# kilo.net
KiCad netlist of a schematic drawn in EAGLE
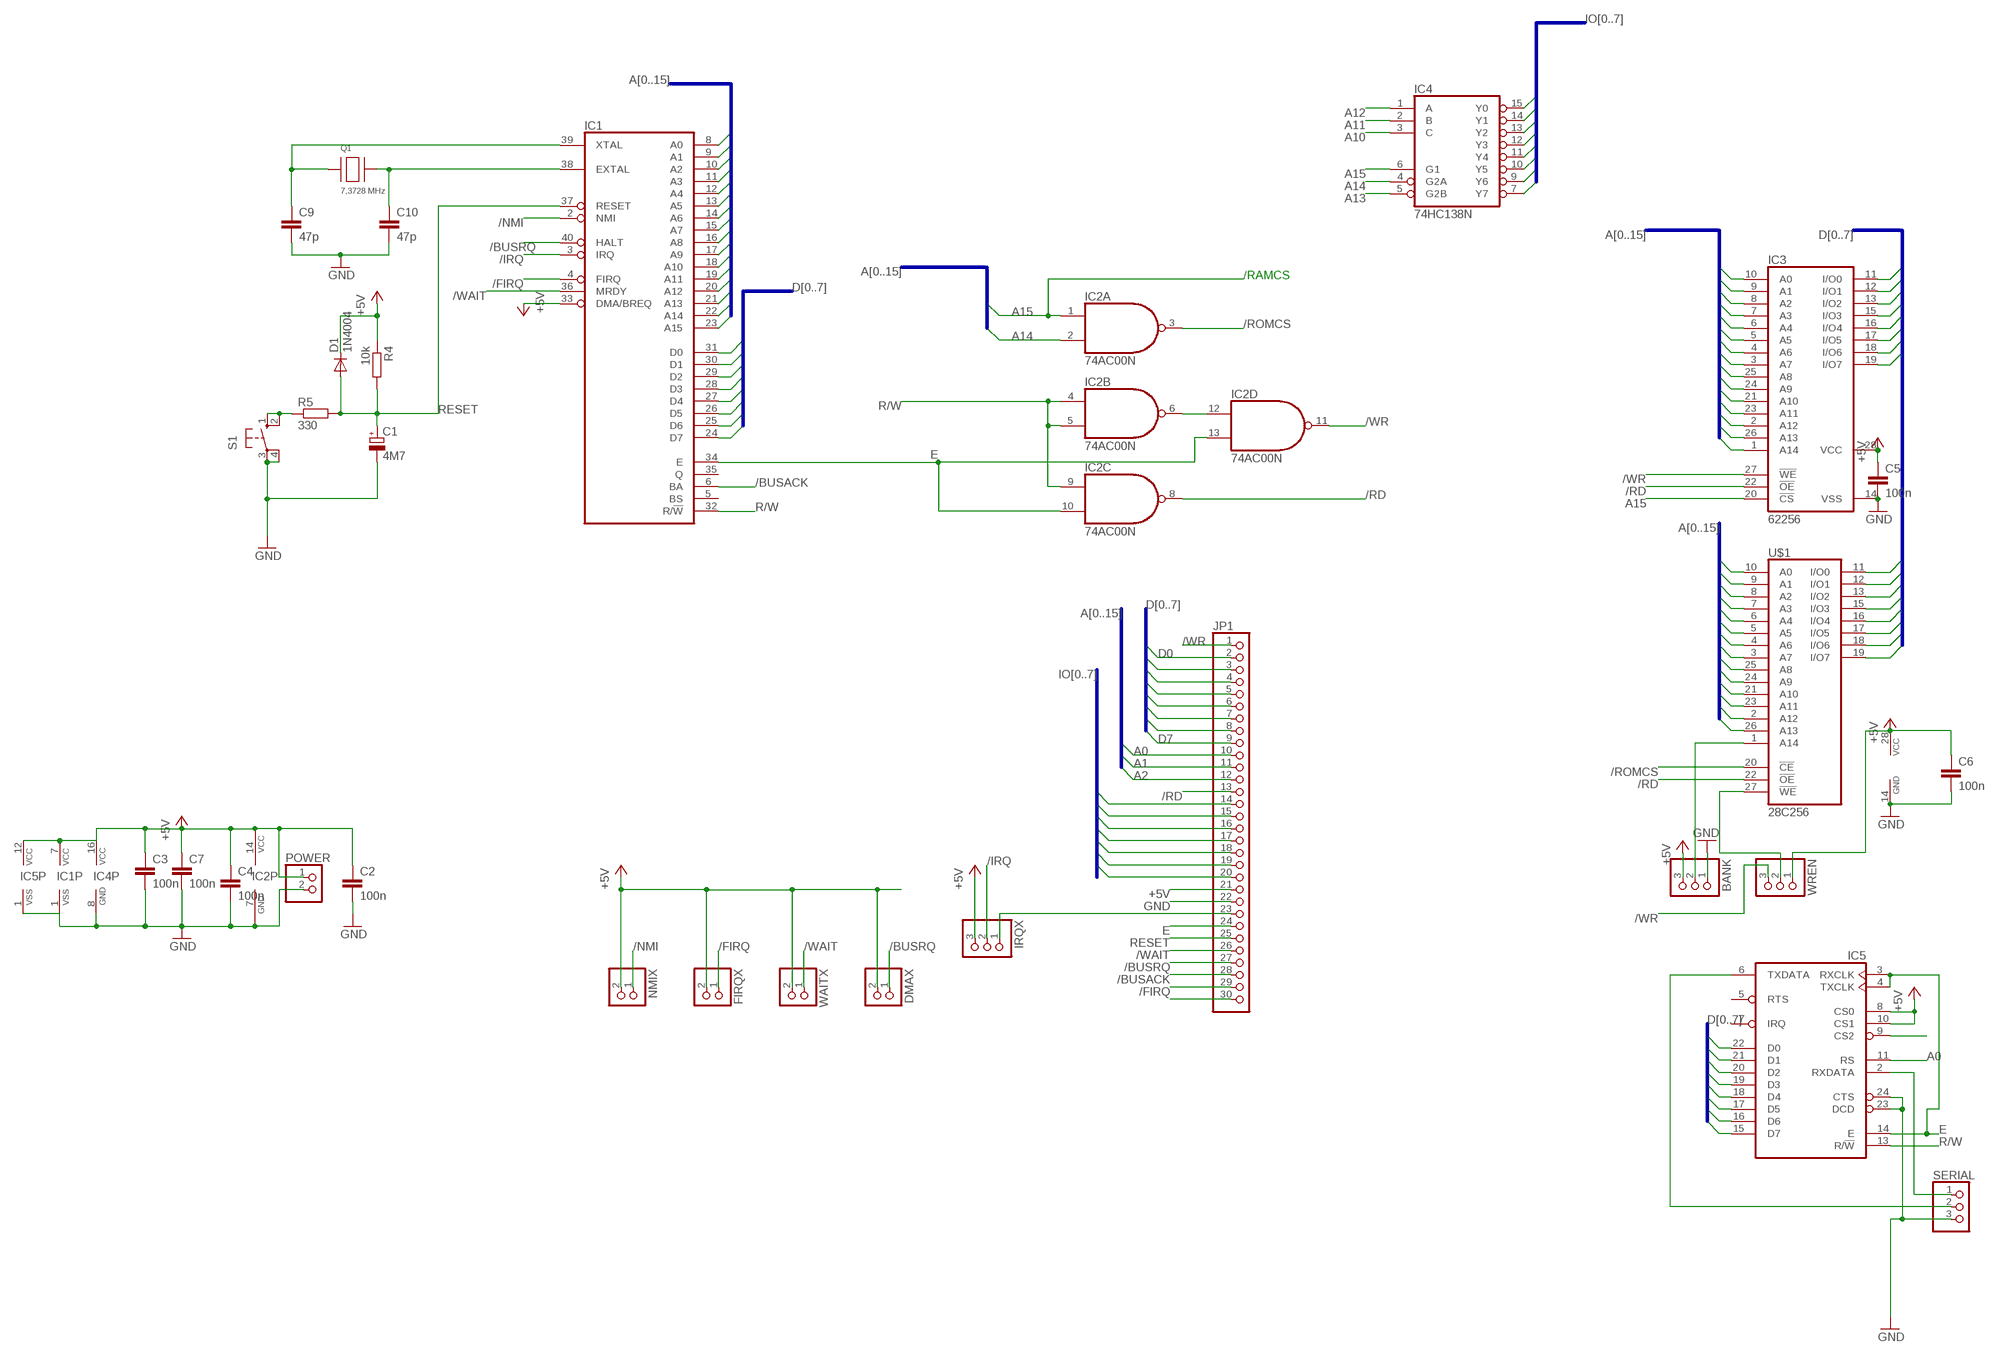
[diagram p0: schematic, sheet 1]

(export (version "E")
  (design (tool "Eeschema 10.0.6"))
  (components
    (comp (ref "BANK")
      (value "PINHD-1X3")
      (footprint "eagle-import:1X03")
      (libsource (lib "eagle-import") (part "PINHD-1X3"))
    )
    (comp (ref "C1")
      (value "4M7")
      (footprint "eagle-import:E2,5-6")
      (libsource (lib "eagle-import") (part "CPOL-EUE2.5-6"))
    )
    (comp (ref "C2")
      (value "100n")
      (footprint "eagle-import:C025-030X050")
      (libsource (lib "eagle-import") (part "C-EU025-030X050"))
    )
    (comp (ref "C3")
      (value "100n")
      (footprint "eagle-import:C025-030X050")
      (libsource (lib "eagle-import") (part "C-EU025-030X050"))
    )
    (comp (ref "C4")
      (value "100n")
      (footprint "eagle-import:C025-030X050")
      (libsource (lib "eagle-import") (part "C-EU025-030X050"))
    )
    (comp (ref "C5")
      (value "100n")
      (footprint "eagle-import:C025-030X050")
      (libsource (lib "eagle-import") (part "C-EU025-030X050"))
    )
    (comp (ref "C6")
      (value "100n")
      (footprint "eagle-import:C025-030X050")
      (libsource (lib "eagle-import") (part "C-EU025-030X050"))
    )
    (comp (ref "C7")
      (value "100n")
      (footprint "eagle-import:C025-030X050")
      (libsource (lib "eagle-import") (part "C-EU025-030X050"))
    )
    (comp (ref "C9")
      (value "47p")
      (footprint "eagle-import:C025-030X050")
      (libsource (lib "eagle-import") (part "C-EU025-030X050"))
    )
    (comp (ref "C10")
      (value "47p")
      (footprint "eagle-import:C025-030X050")
      (libsource (lib "eagle-import") (part "C-EU025-030X050"))
    )
    (comp (ref "D1")
      (value "1N4004")
      (footprint "eagle-import:DO41-10")
      (libsource (lib "eagle-import") (part "1N4004"))
    )
    (comp (ref "DMAX")
      (value "PINHD-1X2")
      (footprint "eagle-import:1X02")
      (libsource (lib "eagle-import") (part "PINHD-1X2"))
    )
    (comp (ref "FIRQX")
      (value "PINHD-1X2")
      (footprint "eagle-import:1X02")
      (libsource (lib "eagle-import") (part "PINHD-1X2"))
    )
    (comp (ref "IC1")
      (value "6809")
      (footprint "eagle-import:DIL40")
      (fields (field (name "MF") "NTE ELECTRONICS") (field (name "MPN") "NTE6809"))
      (libsource (lib "eagle-import") (part "6809"))
    )
    (comp (ref "IC2")
      (value "74AC00N")
      (footprint "eagle-import:DIL14")
      (libsource (lib "eagle-import") (part "7400NALS"))
    )
    (comp (ref "IC3")
      (value "62256")
      (footprint "eagle-import:DIL28-6")
      (libsource (lib "eagle-import") (part "62256P"))
    )
    (comp (ref "IC4")
      (value "74HC138N")
      (footprint "eagle-import:DIL16")
      (libsource (lib "eagle-import") (part "74138NHC"))
    )
    (comp (ref "IC5")
      (value "6850")
      (footprint "eagle-import:DIL24")
      (fields (field (name "MF") "NTE ELECTRONICS") (field (name "MPN") "NTE6850"))
      (libsource (lib "eagle-import") (part "6850"))
    )
    (comp (ref "IRQX")
      (value "PINHD-1X3")
      (footprint "eagle-import:1X03")
      (libsource (lib "eagle-import") (part "PINHD-1X3"))
    )
    (comp (ref "JP1")
      (value "PINHD-1X30")
      (footprint "eagle-import:1X30")
      (libsource (lib "eagle-import") (part "PINHD-1X30"))
    )
    (comp (ref "NMIX")
      (value "PINHD-1X2")
      (footprint "eagle-import:1X02")
      (libsource (lib "eagle-import") (part "PINHD-1X2"))
    )
    (comp (ref "POWER")
      (value "PINHD-1X2")
      (footprint "eagle-import:1X02")
      (libsource (lib "eagle-import") (part "PINHD-1X2"))
    )
    (comp (ref "Q1")
      (value "7,3728 MHz")
      (footprint "eagle-import:HC49US")
      (libsource (lib "eagle-import") (part "306010080_XTAL_8MHZ_HC49US"))
    )
    (comp (ref "R4")
      (value "10k")
      (footprint "eagle-import:0207_7")
      (libsource (lib "eagle-import") (part "R-EU_0207/7"))
    )
    (comp (ref "R5")
      (value "330")
      (footprint "eagle-import:0207_7")
      (libsource (lib "eagle-import") (part "R-EU_0207/7"))
    )
    (comp (ref "S1")
      (value "40-XX")
      (footprint "eagle-import:B3F-40XX")
      (fields (field (name "MF") "OMRON COMPONENTS USA") (field (name "MPN") "B3F-4000"))
      (libsource (lib "eagle-import") (part "40-XX"))
    )
    (comp (ref "SERIAL")
      (value "PINHD-1X3")
      (footprint "eagle-import:1X03")
      (libsource (lib "eagle-import") (part "PINHD-1X3"))
    )
    (comp (ref "U$1")
      (value "28C256")
      (footprint "eagle-import:DIL28")
      (libsource (lib "eagle-import") (part "28C256"))
    )
    (comp (ref "WAITX")
      (value "PINHD-1X2")
      (footprint "eagle-import:1X02")
      (libsource (lib "eagle-import") (part "PINHD-1X2"))
    )
    (comp (ref "WREN")
      (value "PINHD-1X3")
      (footprint "eagle-import:1X03")
      (libsource (lib "eagle-import") (part "PINHD-1X3"))
    )
  )
  (nets
    (net (code "1") (name "+5V") (class "Default")
      (node (ref "BANK") (pin "3") (pinfunction "3_3") (pintype "passive"))
      (node (ref "C2") (pin "1") (pinfunction "1_1") (pintype "passive"))
      (node (ref "C3") (pin "1") (pinfunction "1_1") (pintype "passive"))
      (node (ref "C4") (pin "1") (pinfunction "1_1") (pintype "passive"))
      (node (ref "C5") (pin "1") (pinfunction "1_1") (pintype "passive"))
      (node (ref "C6") (pin "1") (pinfunction "1_1") (pintype "passive"))
      (node (ref "C7") (pin "1") (pinfunction "1_1") (pintype "passive"))
      (node (ref "D1") (pin "C") (pinfunction "C_C") (pintype "passive"))
      (node (ref "DMAX") (pin "2") (pinfunction "2_2") (pintype "passive"))
      (node (ref "FIRQX") (pin "2") (pinfunction "2_2") (pintype "passive"))
      (node (ref "IC1") (pin "33") (pinfunction "DMA/BREQ_33") (pintype "input"))
      (node (ref "IC1") (pin "7") (pinfunction "VCC_7") (pintype "power_in"))
      (node (ref "IC2") (pin "14") (pinfunction "VCC_14") (pintype "power_in"))
      (node (ref "IC3") (pin "28") (pinfunction "VCC_28") (pintype "power_in"))
      (node (ref "IC4") (pin "16") (pinfunction "VCC_16") (pintype "power_in"))
      (node (ref "IC5") (pin "10") (pinfunction "CS1_10") (pintype "input"))
      (node (ref "IC5") (pin "12") (pinfunction "VCC_12") (pintype "power_in"))
      (node (ref "IC5") (pin "8") (pinfunction "CS0_8") (pintype "input"))
      (node (ref "IRQX") (pin "3") (pinfunction "3_3") (pintype "passive"))
      (node (ref "JP1") (pin "21") (pinfunction "21_21") (pintype "passive"))
      (node (ref "NMIX") (pin "2") (pinfunction "2_2") (pintype "passive"))
      (node (ref "POWER") (pin "1") (pinfunction "1_1") (pintype "passive"))
      (node (ref "R4") (pin "1") (pinfunction "1_1") (pintype "passive"))
      (node (ref "U$1") (pin "28") (pinfunction "VCC_28") (pintype "power_in"))
      (node (ref "WAITX") (pin "2") (pinfunction "2_2") (pintype "passive"))
      (node (ref "WREN") (pin "1") (pinfunction "1_1") (pintype "passive"))
    )
    (net (code "5") (name "A0") (class "Default")
      (node (ref "IC1") (pin "8") (pinfunction "A0_8") (pintype "tri_state"))
      (node (ref "IC3") (pin "10") (pinfunction "A0_10") (pintype "input"))
      (node (ref "IC5") (pin "11") (pinfunction "RS_11") (pintype "input"))
      (node (ref "JP1") (pin "10") (pinfunction "10_10") (pintype "passive"))
      (node (ref "U$1") (pin "10") (pinfunction "A0_10") (pintype "input"))
    )
    (net (code "6") (name "A1") (class "Default")
      (node (ref "IC1") (pin "9") (pinfunction "A1_9") (pintype "tri_state"))
      (node (ref "IC3") (pin "9") (pinfunction "A1_9") (pintype "input"))
      (node (ref "JP1") (pin "11") (pinfunction "11_11") (pintype "passive"))
      (node (ref "U$1") (pin "9") (pinfunction "A1_9") (pintype "input"))
    )
    (net (code "7") (name "A2") (class "Default")
      (node (ref "IC1") (pin "10") (pinfunction "A2_10") (pintype "tri_state"))
      (node (ref "IC3") (pin "8") (pinfunction "A2_8") (pintype "input"))
      (node (ref "JP1") (pin "12") (pinfunction "12_12") (pintype "passive"))
      (node (ref "U$1") (pin "8") (pinfunction "A2_8") (pintype "input"))
    )
    (net (code "8") (name "A3") (class "Default")
      (node (ref "IC1") (pin "11") (pinfunction "A3_11") (pintype "tri_state"))
      (node (ref "IC3") (pin "7") (pinfunction "A3_7") (pintype "input"))
      (node (ref "U$1") (pin "7") (pinfunction "A3_7") (pintype "input"))
    )
    (net (code "9") (name "A4") (class "Default")
      (node (ref "IC1") (pin "12") (pinfunction "A4_12") (pintype "tri_state"))
      (node (ref "IC3") (pin "6") (pinfunction "A4_6") (pintype "input"))
      (node (ref "U$1") (pin "6") (pinfunction "A4_6") (pintype "input"))
    )
    (net (code "10") (name "A5") (class "Default")
      (node (ref "IC1") (pin "13") (pinfunction "A5_13") (pintype "tri_state"))
      (node (ref "IC3") (pin "5") (pinfunction "A5_5") (pintype "input"))
      (node (ref "U$1") (pin "5") (pinfunction "A5_5") (pintype "input"))
    )
    (net (code "11") (name "A6") (class "Default")
      (node (ref "IC1") (pin "14") (pinfunction "A6_14") (pintype "tri_state"))
      (node (ref "IC3") (pin "4") (pinfunction "A6_4") (pintype "input"))
      (node (ref "U$1") (pin "4") (pinfunction "A6_4") (pintype "input"))
    )
    (net (code "12") (name "A7") (class "Default")
      (node (ref "IC1") (pin "15") (pinfunction "A7_15") (pintype "tri_state"))
      (node (ref "IC3") (pin "3") (pinfunction "A7_3") (pintype "input"))
      (node (ref "U$1") (pin "3") (pinfunction "A7_3") (pintype "input"))
    )
    (net (code "13") (name "A8") (class "Default")
      (node (ref "IC1") (pin "16") (pinfunction "A8_16") (pintype "tri_state"))
      (node (ref "IC3") (pin "25") (pinfunction "A8_25") (pintype "input"))
      (node (ref "U$1") (pin "25") (pinfunction "A8_25") (pintype "input"))
    )
    (net (code "14") (name "A9") (class "Default")
      (node (ref "IC1") (pin "17") (pinfunction "A9_17") (pintype "tri_state"))
      (node (ref "IC3") (pin "24") (pinfunction "A9_24") (pintype "input"))
      (node (ref "U$1") (pin "24") (pinfunction "A9_24") (pintype "input"))
    )
    (net (code "15") (name "A10") (class "Default")
      (node (ref "IC1") (pin "18") (pinfunction "A10_18") (pintype "tri_state"))
      (node (ref "IC3") (pin "21") (pinfunction "A10_21") (pintype "input"))
      (node (ref "IC4") (pin "3") (pinfunction "C_3") (pintype "input"))
      (node (ref "U$1") (pin "21") (pinfunction "A10_21") (pintype "input"))
    )
    (net (code "16") (name "A11") (class "Default")
      (node (ref "IC1") (pin "19") (pinfunction "A11_19") (pintype "tri_state"))
      (node (ref "IC3") (pin "23") (pinfunction "A11_23") (pintype "input"))
      (node (ref "IC4") (pin "2") (pinfunction "B_2") (pintype "input"))
      (node (ref "U$1") (pin "23") (pinfunction "A11_23") (pintype "input"))
    )
    (net (code "17") (name "A12") (class "Default")
      (node (ref "IC1") (pin "20") (pinfunction "A12_20") (pintype "tri_state"))
      (node (ref "IC3") (pin "2") (pinfunction "A12_2") (pintype "input"))
      (node (ref "IC4") (pin "1") (pinfunction "A_1") (pintype "input"))
      (node (ref "U$1") (pin "2") (pinfunction "A12_2") (pintype "input"))
    )
    (net (code "18") (name "A13") (class "Default")
      (node (ref "IC1") (pin "21") (pinfunction "A13_21") (pintype "tri_state"))
      (node (ref "IC3") (pin "26") (pinfunction "A13_26") (pintype "input"))
      (node (ref "IC4") (pin "5") (pinfunction "G2B_5") (pintype "input"))
      (node (ref "U$1") (pin "26") (pinfunction "A13_26") (pintype "input"))
    )
    (net (code "19") (name "A14") (class "Default")
      (node (ref "IC1") (pin "22") (pinfunction "A14_22") (pintype "tri_state"))
      (node (ref "IC2") (pin "2") (pinfunction "I1_2") (pintype "input"))
      (node (ref "IC3") (pin "1") (pinfunction "A14_1") (pintype "input"))
      (node (ref "IC4") (pin "4") (pinfunction "G2A_4") (pintype "input"))
    )
    (net (code "20") (name "A15") (class "Default")
      (node (ref "IC1") (pin "23") (pinfunction "A15_23") (pintype "tri_state"))
      (node (ref "IC2") (pin "1") (pinfunction "I0_1") (pintype "input"))
      (node (ref "IC3") (pin "20") (pinfunction "~{CS}_20") (pintype "input"))
      (node (ref "IC4") (pin "6") (pinfunction "G1_6") (pintype "input"))
    )
    (net (code "21") (name "D0") (class "Default")
      (node (ref "IC1") (pin "31") (pinfunction "D0_31") (pintype "bidirectional"))
      (node (ref "IC3") (pin "11") (pinfunction "I/O0_11") (pintype "bidirectional"))
      (node (ref "IC5") (pin "22") (pinfunction "D0_22") (pintype "bidirectional"))
      (node (ref "JP1") (pin "2") (pinfunction "2_2") (pintype "passive"))
      (node (ref "U$1") (pin "11") (pinfunction "I/O0_11") (pintype "tri_state"))
    )
    (net (code "22") (name "D1") (class "Default")
      (node (ref "IC1") (pin "30") (pinfunction "D1_30") (pintype "bidirectional"))
      (node (ref "IC3") (pin "12") (pinfunction "I/O1_12") (pintype "bidirectional"))
      (node (ref "IC5") (pin "21") (pinfunction "D1_21") (pintype "bidirectional"))
      (node (ref "JP1") (pin "3") (pinfunction "3_3") (pintype "passive"))
      (node (ref "U$1") (pin "12") (pinfunction "I/O1_12") (pintype "tri_state"))
    )
    (net (code "23") (name "D2") (class "Default")
      (node (ref "IC1") (pin "29") (pinfunction "D2_29") (pintype "bidirectional"))
      (node (ref "IC3") (pin "13") (pinfunction "I/O2_13") (pintype "bidirectional"))
      (node (ref "IC5") (pin "20") (pinfunction "D2_20") (pintype "bidirectional"))
      (node (ref "JP1") (pin "4") (pinfunction "4_4") (pintype "passive"))
      (node (ref "U$1") (pin "13") (pinfunction "I/O2_13") (pintype "tri_state"))
    )
    (net (code "24") (name "D3") (class "Default")
      (node (ref "IC1") (pin "28") (pinfunction "D3_28") (pintype "bidirectional"))
      (node (ref "IC3") (pin "15") (pinfunction "I/O3_15") (pintype "bidirectional"))
      (node (ref "IC5") (pin "19") (pinfunction "D3_19") (pintype "bidirectional"))
      (node (ref "JP1") (pin "5") (pinfunction "5_5") (pintype "passive"))
      (node (ref "U$1") (pin "15") (pinfunction "I/O3_15") (pintype "tri_state"))
    )
    (net (code "25") (name "D4") (class "Default")
      (node (ref "IC1") (pin "27") (pinfunction "D4_27") (pintype "bidirectional"))
      (node (ref "IC3") (pin "16") (pinfunction "I/O4_16") (pintype "bidirectional"))
      (node (ref "IC5") (pin "18") (pinfunction "D4_18") (pintype "bidirectional"))
      (node (ref "JP1") (pin "6") (pinfunction "6_6") (pintype "passive"))
      (node (ref "U$1") (pin "16") (pinfunction "I/O4_16") (pintype "tri_state"))
    )
    (net (code "26") (name "D5") (class "Default")
      (node (ref "IC1") (pin "26") (pinfunction "D5_26") (pintype "bidirectional"))
      (node (ref "IC3") (pin "17") (pinfunction "I/O5_17") (pintype "bidirectional"))
      (node (ref "IC5") (pin "17") (pinfunction "D5_17") (pintype "bidirectional"))
      (node (ref "JP1") (pin "7") (pinfunction "7_7") (pintype "passive"))
      (node (ref "U$1") (pin "17") (pinfunction "I/O5_17") (pintype "tri_state"))
    )
    (net (code "27") (name "D6") (class "Default")
      (node (ref "IC1") (pin "25") (pinfunction "D6_25") (pintype "bidirectional"))
      (node (ref "IC3") (pin "18") (pinfunction "I/O6_18") (pintype "bidirectional"))
      (node (ref "IC5") (pin "16") (pinfunction "D6_16") (pintype "bidirectional"))
      (node (ref "JP1") (pin "8") (pinfunction "8_8") (pintype "passive"))
      (node (ref "U$1") (pin "18") (pinfunction "I/O6_18") (pintype "tri_state"))
    )
    (net (code "28") (name "D7") (class "Default")
      (node (ref "IC1") (pin "24") (pinfunction "D7_24") (pintype "bidirectional"))
      (node (ref "IC3") (pin "19") (pinfunction "I/O7_19") (pintype "bidirectional"))
      (node (ref "IC5") (pin "15") (pinfunction "D7_15") (pintype "bidirectional"))
      (node (ref "JP1") (pin "9") (pinfunction "9_9") (pintype "passive"))
      (node (ref "U$1") (pin "19") (pinfunction "I/O7_19") (pintype "tri_state"))
    )
    (net (code "29") (name "E") (class "Default")
      (node (ref "IC1") (pin "34") (pinfunction "E_34") (pintype "output"))
      (node (ref "IC2") (pin "10") (pinfunction "I1_10") (pintype "input"))
      (node (ref "IC2") (pin "13") (pinfunction "I1_13") (pintype "input"))
      (node (ref "IC5") (pin "14") (pinfunction "E_14") (pintype "input"))
      (node (ref "IC5") (pin "3") (pinfunction "RXCLK_3") (pintype "input"))
      (node (ref "IC5") (pin "4") (pinfunction "TXCLK_4") (pintype "input"))
      (node (ref "JP1") (pin "24") (pinfunction "24_24") (pintype "passive"))
    )
    (net (code "30") (name "GND") (class "Default")
      (node (ref "BANK") (pin "1") (pinfunction "1_1") (pintype "passive"))
      (node (ref "C1") (pin "-") (pinfunction "-_-") (pintype "passive"))
      (node (ref "C10") (pin "2") (pinfunction "2_2") (pintype "passive"))
      (node (ref "C2") (pin "2") (pinfunction "2_2") (pintype "passive"))
      (node (ref "C3") (pin "2") (pinfunction "2_2") (pintype "passive"))
      (node (ref "C4") (pin "2") (pinfunction "2_2") (pintype "passive"))
      (node (ref "C5") (pin "2") (pinfunction "2_2") (pintype "passive"))
      (node (ref "C6") (pin "2") (pinfunction "2_2") (pintype "passive"))
      (node (ref "C7") (pin "2") (pinfunction "2_2") (pintype "passive"))
      (node (ref "C9") (pin "2") (pinfunction "2_2") (pintype "passive"))
      (node (ref "IC1") (pin "1") (pinfunction "VSS_1") (pintype "power_in"))
      (node (ref "IC2") (pin "7") (pinfunction "GND_7") (pintype "power_in"))
      (node (ref "IC3") (pin "14") (pinfunction "VSS_14") (pintype "power_in"))
      (node (ref "IC4") (pin "8") (pinfunction "GND_8") (pintype "power_in"))
      (node (ref "IC5") (pin "1") (pinfunction "VSS_1") (pintype "power_in"))
      (node (ref "IC5") (pin "23") (pinfunction "DCD_23") (pintype "input"))
      (node (ref "IC5") (pin "24") (pinfunction "CTS_24") (pintype "input"))
      (node (ref "JP1") (pin "22") (pinfunction "22_22") (pintype "passive"))
      (node (ref "POWER") (pin "2") (pinfunction "2_2") (pintype "passive"))
      (node (ref "S1") (pin "3") (pinfunction "P_3") (pintype "passive"))
      (node (ref "S1") (pin "4") (pinfunction "P1_4") (pintype "passive"))
      (node (ref "SERIAL") (pin "3") (pinfunction "3_3") (pintype "passive"))
      (node (ref "U$1") (pin "14") (pinfunction "GND_14") (pintype "power_in"))
    )
    (net (code "31") (name "IO0") (class "Default")
      (node (ref "IC4") (pin "15") (pinfunction "Y0_15") (pintype "output"))
      (node (ref "IC5") (pin "9") (pinfunction "CS2_9") (pintype "input"))
    )
    (net (code "32") (name "IO1") (class "Default")
      (node (ref "IC4") (pin "14") (pinfunction "Y1_14") (pintype "output"))
      (node (ref "JP1") (pin "14") (pinfunction "14_14") (pintype "passive"))
    )
    (net (code "33") (name "IO2") (class "Default")
      (node (ref "IC4") (pin "13") (pinfunction "Y2_13") (pintype "output"))
      (node (ref "JP1") (pin "15") (pinfunction "15_15") (pintype "passive"))
    )
    (net (code "34") (name "IO3") (class "Default")
      (node (ref "IC4") (pin "12") (pinfunction "Y3_12") (pintype "output"))
      (node (ref "JP1") (pin "16") (pinfunction "16_16") (pintype "passive"))
    )
    (net (code "35") (name "IO4") (class "Default")
      (node (ref "IC4") (pin "11") (pinfunction "Y4_11") (pintype "output"))
      (node (ref "JP1") (pin "17") (pinfunction "17_17") (pintype "passive"))
    )
    (net (code "36") (name "IO5") (class "Default")
      (node (ref "IC4") (pin "10") (pinfunction "Y5_10") (pintype "output"))
      (node (ref "JP1") (pin "18") (pinfunction "18_18") (pintype "passive"))
    )
    (net (code "37") (name "IO6") (class "Default")
      (node (ref "IC4") (pin "9") (pinfunction "Y6_9") (pintype "output"))
      (node (ref "JP1") (pin "19") (pinfunction "19_19") (pintype "passive"))
    )
    (net (code "38") (name "IO7") (class "Default")
      (node (ref "IC4") (pin "7") (pinfunction "Y7_7") (pintype "output"))
      (node (ref "JP1") (pin "20") (pinfunction "20_20") (pintype "passive"))
    )
    (net (code "39") (name "Net-(IC1A-EXTAL)") (class "Default")
      (node (ref "C10") (pin "1") (pinfunction "1_1") (pintype "passive"))
      (node (ref "IC1") (pin "38") (pinfunction "EXTAL_38") (pintype "input"))
      (node (ref "Q1") (pin "P$2") (pinfunction "P$2_P$2") (pintype "passive"))
    )
    (net (code "40") (name "Net-(IC1A-XTAL)") (class "Default")
      (node (ref "C9") (pin "1") (pinfunction "1_1") (pintype "passive"))
      (node (ref "IC1") (pin "39") (pinfunction "XTAL_39") (pintype "input"))
      (node (ref "Q1") (pin "P$1") (pinfunction "P$1_P$1") (pintype "passive"))
    )
    (net (code "41") (name "Net-(IC2B-O)") (class "Default")
      (node (ref "IC2") (pin "12") (pinfunction "I0_12") (pintype "input"))
      (node (ref "IC2") (pin "6") (pinfunction "O_6") (pintype "output"))
    )
    (net (code "42") (name "Net-(IC5A-RXDATA)") (class "Default")
      (node (ref "IC5") (pin "2") (pinfunction "RXDATA_2") (pintype "input"))
      (node (ref "SERIAL") (pin "1") (pinfunction "1_1") (pintype "passive"))
    )
    (net (code "43") (name "Net-(IC5A-TXDATA)") (class "Default")
      (node (ref "IC5") (pin "6") (pinfunction "TXDATA_6") (pintype "output"))
      (node (ref "SERIAL") (pin "2") (pinfunction "2_2") (pintype "passive"))
    )
    (net (code "44") (name "Net-(IRQX-Pad1)") (class "Default")
      (node (ref "IRQX") (pin "1") (pinfunction "1_1") (pintype "passive"))
      (node (ref "JP1") (pin "23") (pinfunction "23_23") (pintype "passive"))
    )
    (net (code "45") (name "Net-(S1-S)") (class "Default")
      (node (ref "R5") (pin "1") (pinfunction "1_1") (pintype "passive"))
      (node (ref "S1") (pin "1") (pinfunction "S_1") (pintype "passive"))
      (node (ref "S1") (pin "2") (pinfunction "S1_2") (pintype "passive"))
    )
    (net (code "46") (name "Net-(U$1A-A14)") (class "Default")
      (node (ref "BANK") (pin "2") (pinfunction "2_2") (pintype "passive"))
      (node (ref "U$1") (pin "1") (pinfunction "A14_1") (pintype "input"))
    )
    (net (code "47") (name "Net-(U$1A-~{WE})") (class "Default")
      (node (ref "U$1") (pin "27") (pinfunction "~{WE}_27") (pintype "input"))
      (node (ref "WREN") (pin "2") (pinfunction "2_2") (pintype "passive"))
    )
    (net (code "48") (name "RESET") (class "Default")
      (node (ref "C1") (pin "+") (pinfunction "+_+") (pintype "passive"))
      (node (ref "D1") (pin "A") (pinfunction "A_A") (pintype "passive"))
      (node (ref "IC1") (pin "37") (pinfunction "RESET_37") (pintype "input"))
      (node (ref "JP1") (pin "25") (pinfunction "25_25") (pintype "passive"))
      (node (ref "R4") (pin "2") (pinfunction "2_2") (pintype "passive"))
      (node (ref "R5") (pin "2") (pinfunction "2_2") (pintype "passive"))
    )
    (net (code "49") (name "R{slash}W") (class "Default")
      (node (ref "IC1") (pin "32") (pinfunction "R/~{W}_32") (pintype "output"))
      (node (ref "IC2") (pin "4") (pinfunction "I0_4") (pintype "input"))
      (node (ref "IC2") (pin "5") (pinfunction "I1_5") (pintype "input"))
      (node (ref "IC2") (pin "9") (pinfunction "I0_9") (pintype "input"))
      (node (ref "IC5") (pin "13") (pinfunction "R/~{W}_13") (pintype "input"))
    )
    (net (code "50") (name "unconnected-(IC1A-BS-Pad5)") (class "Default")
      (node (ref "IC1") (pin "5") (pinfunction "BS_5") (pintype "output"))
    )
    (net (code "51") (name "unconnected-(IC1A-Q-Pad35)") (class "Default")
      (node (ref "IC1") (pin "35") (pinfunction "Q_35") (pintype "output"))
    )
    (net (code "52") (name "unconnected-(IC5A-IRQ-Pad7)") (class "Default")
      (node (ref "IC5") (pin "7") (pinfunction "IRQ_7") (pintype "output"))
    )
    (net (code "53") (name "unconnected-(IC5A-RTS-Pad5)") (class "Default")
      (node (ref "IC5") (pin "5") (pinfunction "RTS_5") (pintype "output"))
    )
    (net (code "54") (name "unconnected-(JP1-Pad30)") (class "Default")
      (node (ref "JP1") (pin "30") (pinfunction "30_30") (pintype "passive"))
    )
    (net (code "55") (name "{slash}BUSACK") (class "Default")
      (node (ref "IC1") (pin "6") (pinfunction "BA_6") (pintype "output"))
      (node (ref "JP1") (pin "28") (pinfunction "28_28") (pintype "passive"))
    )
    (net (code "56") (name "{slash}BUSRQ") (class "Default")
      (node (ref "DMAX") (pin "1") (pinfunction "1_1") (pintype "passive"))
      (node (ref "IC1") (pin "40") (pinfunction "HALT_40") (pintype "input"))
      (node (ref "JP1") (pin "27") (pinfunction "27_27") (pintype "passive"))
    )
    (net (code "57") (name "{slash}FIRQ") (class "Default")
      (node (ref "FIRQX") (pin "1") (pinfunction "1_1") (pintype "passive"))
      (node (ref "IC1") (pin "4") (pinfunction "FIRQ_4") (pintype "input"))
      (node (ref "JP1") (pin "29") (pinfunction "29_29") (pintype "passive"))
    )
    (net (code "58") (name "{slash}IRQ") (class "Default")
      (node (ref "IC1") (pin "3") (pinfunction "IRQ_3") (pintype "input"))
      (node (ref "IRQX") (pin "2") (pinfunction "2_2") (pintype "passive"))
    )
    (net (code "59") (name "{slash}NMI") (class "Default")
      (node (ref "IC1") (pin "2") (pinfunction "NMI_2") (pintype "input"))
      (node (ref "NMIX") (pin "1") (pinfunction "1_1") (pintype "passive"))
    )
    (net (code "60") (name "{slash}RD") (class "Default")
      (node (ref "IC2") (pin "8") (pinfunction "O_8") (pintype "output"))
      (node (ref "IC3") (pin "22") (pinfunction "~{OE}_22") (pintype "input"))
      (node (ref "JP1") (pin "13") (pinfunction "13_13") (pintype "passive"))
      (node (ref "U$1") (pin "22") (pinfunction "~{OE}_22") (pintype "input"))
    )
    (net (code "61") (name "{slash}ROMCS") (class "Default")
      (node (ref "IC2") (pin "3") (pinfunction "O_3") (pintype "output"))
      (node (ref "U$1") (pin "20") (pinfunction "~{CE}_20") (pintype "input"))
    )
    (net (code "62") (name "{slash}WAIT") (class "Default")
      (node (ref "IC1") (pin "36") (pinfunction "MRDY_36") (pintype "input"))
      (node (ref "JP1") (pin "26") (pinfunction "26_26") (pintype "passive"))
      (node (ref "WAITX") (pin "1") (pinfunction "1_1") (pintype "passive"))
    )
    (net (code "63") (name "{slash}WR") (class "Default")
      (node (ref "IC2") (pin "11") (pinfunction "O_11") (pintype "output"))
      (node (ref "IC3") (pin "27") (pinfunction "~{WE}_27") (pintype "input"))
      (node (ref "JP1") (pin "1") (pinfunction "1_1") (pintype "passive"))
      (node (ref "WREN") (pin "3") (pinfunction "3_3") (pintype "passive"))
    )
  )
)
